# power_supply.net
KiCad netlist of a schematic drawn in Altium Designer
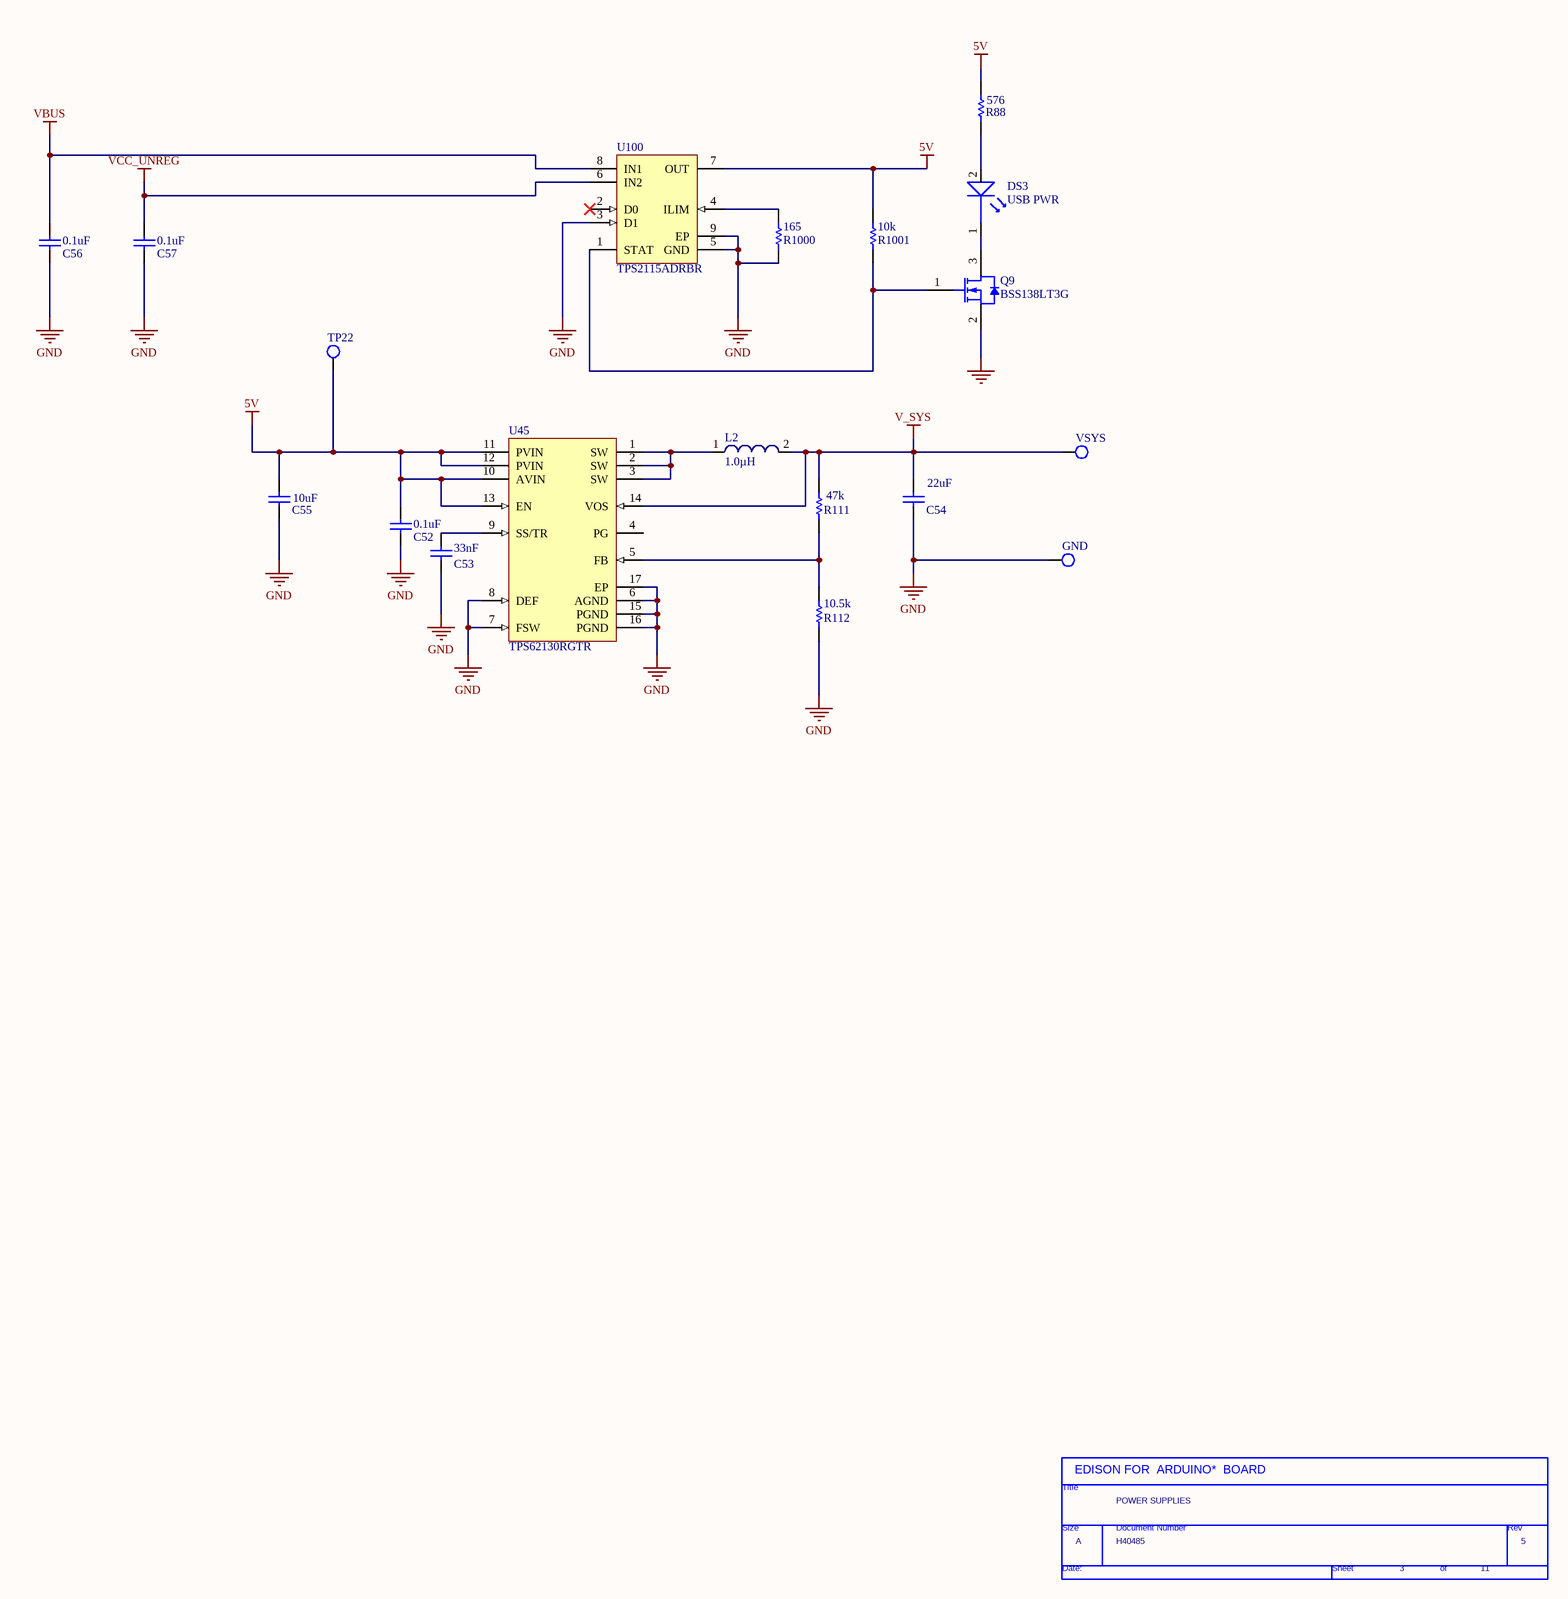
[diagram p0: power_supply.SchDoc]

(export (version "E")
  (design (tool "Eeschema 10.0.6"))
  (components
    (comp (ref "C52")
      (value "0.1uF")
      (footprint "CAPC0805(2012)145_L")
      (description "CAP 100nF 16V ±10% 0805 (2012 Metric) Thickness 1.45mm SMD")
      (fields (field (name "TOLERANCE") "±10%") (field (name "Comment") "CAP 100nF 16V 0805(2012)"))
      (libsource (lib "Altium Content Vault") (part "CMP-1036-04401-1"))
    )
    (comp (ref "C53")
      (value "33nF")
      (footprint "CAPC0805(2012)145_L")
      (description "CAP 33nF 50V ±10% 0805 (2012 Metric) Thickness 1.45mm SMD")
      (fields (field (name "TOLERANCE") "±10%") (field (name "Comment") "CAP 33nF 50V 0805(2012)"))
      (libsource (lib "Altium Content Vault") (part "CMP-1036-04168-1"))
    )
    (comp (ref "C54")
      (value "22uF")
      (footprint "CAPC0805(2012)145_M")
      (description "CAP 22uF 6.3V ±20% 0805 (2012 Metric) Thickness 1.45mm SMD")
      (fields (field (name "TOLERANCE") "±20%") (field (name "Comment") "CAP 22uF 6.3V 0805(2012)"))
      (libsource (lib "Altium Content Vault") (part "CMP-1036-04939-1"))
    )
    (comp (ref "C55")
      (value "10uF")
      (footprint "CAPC0805(2012)145_L")
      (description "CAP 820pF 25V ±10% 0805 (2012 Metric) Thickness 1.45mm SMD")
      (fields (field (name "TOLERANCE") "±10%") (field (name "Comment") "CAP 820pF 25V 0805(2012)"))
      (libsource (lib "Altium Content Vault") (part "CMP-1036-02893-1"))
    )
    (comp (ref "C56")
      (value "0.1uF")
      (footprint "CAPC0805(2012)145_L")
      (description "CAP 100nF 16V ±10% 0805 (2012 Metric) Thickness 1.45mm SMD")
      (fields (field (name "TOLERANCE") "±10%") (field (name "Comment") "CAP 100nF 16V 0805(2012)"))
      (libsource (lib "Altium Content Vault") (part "CMP-1036-04401-1"))
    )
    (comp (ref "C57")
      (value "0.1uF")
      (footprint "CAPC0805(2012)145_L")
      (description "CAP 100nF 16V ±10% 0805 (2012 Metric) Thickness 1.45mm SMD")
      (fields (field (name "TOLERANCE") "±10%") (field (name "Comment") "CAP 100nF 16V 0805(2012)"))
      (libsource (lib "Altium Content Vault") (part "CMP-1036-04401-1"))
    )
    (comp (ref "DS3")
      (value "USB PWR")
      (footprint "LTST-C281KGKT")
      (libsource (lib "elevate_lib") (part "LED_Edison"))
    )
    (comp (ref "GND")
      (value "Testpoint")
      (footprint "Tespoint_Keystone")
      (libsource (lib "elevate_lib") (part "TestPoint"))
    )
    (comp (ref "L2")
      (value "1.0µH")
      (footprint "SMD 2508")
      (description "Power Multilayer Inductor WE-MAPI, L=1.0µH")
      (fields
        (field (name "PARTNO") "74438322010")
        (field (name "MANUFACTURER") "Würth Elektronik eiSos GmbH")
        (field (name "CREATED BY") "Otto Christin")
      )
      (libsource (lib "WE-MAPI_2508") (part "WE-MAPI 2508 ,74438322010"))
    )
    (comp (ref "Q9")
      (value "BSS138LT3G")
      (footprint "ONSC-SOT-23-3-318-08_V")
      (description "Power MOSFET, 200 mA, 50 V, N-Channel, 3-Pin SOT-23, Pb-Free, Tape and Reel")
      (fields (field (name "MANUFACTURER") "On Semiconductor"))
      (libsource (lib "Altium Content Vault") (part "CMP-1058-00765-1"))
    )
    (comp (ref "R88")
      (value "576")
      (footprint "RESC0603(1608)_N")
      (description "576R 0.1W 1% 0603 (1608 Metric)  SMD")
      (fields (field (name "TOLERANCE") "1 %") (field (name "POWER") "0.1 W"))
      (libsource (lib "Altium Content Vault") (part "CMP-1012-00483-1"))
    )
    (comp (ref "R111")
      (value "47k")
      (footprint "RESC0603(1608)_N")
      (description "47K 0.1W 1% 0603 (1608 Metric)  SMD")
      (fields (field (name "POWER") "0.1 W") (field (name "TOLERANCE") "1 %"))
      (libsource (lib "Altium Content Vault") (part "CMP-1012-00699-1"))
    )
    (comp (ref "R112")
      (value "10.5k")
      (footprint "RESC0603(1608)_N")
      (description "10K5 0.1W 1% 0603 (1608 Metric)  SMD")
      (fields (field (name "POWER") "0.1 W") (field (name "TOLERANCE") "1 %"))
      (libsource (lib "Altium Content Vault") (part "CMP-1012-00625-1"))
    )
    (comp (ref "R1000")
      (value "165")
      (footprint "RESC0805(2012)_L")
      (description "165R 0.125W 1% 0805 (2012 Metric)  SMD")
      (fields (field (name "TOLERANCE") "1 %") (field (name "POWER") "0.125 W"))
      (libsource (lib "Altium Content Vault") (part "CMP-1013-00420-1"))
    )
    (comp (ref "R1001")
      (value "10k")
      (footprint "RESC0805(2012)_M")
      (description "10K 0.125W 1% 0805 (2012 Metric)  SMD")
      (fields (field (name "TOLERANCE") "1 %") (field (name "POWER") "0.125 W"))
      (libsource (lib "Altium Content Vault") (part "CMP-1013-00623-1"))
    )
    (comp (ref "TP22")
      (value "Testpoint")
      (footprint "Tespoint_Keystone")
      (libsource (lib "elevate_lib") (part "TestPoint"))
    )
    (comp (ref "U45")
      (value "TPS62130RGTR")
      (footprint "RGT16-1700X1700TP")
      (fields (field (name "MANUFACTURER") "Texas Instruments"))
      (libsource (lib "Altium Content Vault") (part "CMP-0323-00115-2"))
    )
    (comp (ref "U100")
      (value "TPS2115ADRBR")
      (footprint "DRB8-2400X1650TP")
      (fields (field (name "MANUFACTURER") "Texas Instruments"))
      (libsource (lib "TI Power Management Power Multiplexer (MUX)") (part "TPS2115ADRBR"))
    )
    (comp (ref "VSYS")
      (value "Testpoint")
      (footprint "Tespoint_Keystone")
      (libsource (lib "elevate_lib") (part "TestPoint"))
    )
  )
  (nets
    (net (code "1") (name "5V") (class "Default")
      (node (ref "C52") (pin "1") (pinfunction "1_1") (pintype "passive"))
      (node (ref "C55") (pin "2") (pinfunction "2_2") (pintype "passive"))
      (node (ref "R1001") (pin "2") (pinfunction "2_2") (pintype "passive"))
      (node (ref "R88") (pin "2") (pinfunction "2_2") (pintype "passive"))
      (node (ref "TP22") (pin "1") (pinfunction "TP_1") (pintype "passive"))
      (node (ref "U100") (pin "7") (pinfunction "OUT_7") (pintype "power_in"))
      (node (ref "U45") (pin "10") (pinfunction "AVIN_10") (pintype "power_in"))
      (node (ref "U45") (pin "11") (pinfunction "PVIN_11") (pintype "power_in"))
      (node (ref "U45") (pin "12") (pinfunction "PVIN_12") (pintype "power_in"))
      (node (ref "U45") (pin "13") (pinfunction "EN_13") (pintype "input"))
    )
    (net (code "2") (name "GND") (class "Default")
      (node (ref "C52") (pin "2") (pinfunction "2_2") (pintype "passive"))
      (node (ref "C53") (pin "1") (pinfunction "1_1") (pintype "passive"))
      (node (ref "C54") (pin "1") (pinfunction "1_1") (pintype "passive"))
      (node (ref "C55") (pin "1") (pinfunction "1_1") (pintype "passive"))
      (node (ref "C56") (pin "2") (pinfunction "2_2") (pintype "passive"))
      (node (ref "C57") (pin "2") (pinfunction "2_2") (pintype "passive"))
      (node (ref "GND") (pin "1") (pinfunction "TP_1") (pintype "passive"))
      (node (ref "Q9") (pin "2") (pinfunction "S_2") (pintype "passive"))
      (node (ref "R1000") (pin "1") (pinfunction "1_1") (pintype "passive"))
      (node (ref "R112") (pin "1") (pinfunction "1_1") (pintype "passive"))
      (node (ref "U100") (pin "3") (pinfunction "D1_3") (pintype "input"))
      (node (ref "U100") (pin "5") (pinfunction "GND_5") (pintype "power_in"))
      (node (ref "U100") (pin "9") (pinfunction "EP_9") (pintype "power_in"))
      (node (ref "U45") (pin "15") (pinfunction "PGND_15") (pintype "power_in"))
      (node (ref "U45") (pin "16") (pinfunction "PGND_16") (pintype "power_in"))
      (node (ref "U45") (pin "17") (pinfunction "EP_17") (pintype "power_in"))
      (node (ref "U45") (pin "6") (pinfunction "AGND_6") (pintype "power_in"))
      (node (ref "U45") (pin "7") (pinfunction "FSW_7") (pintype "input"))
      (node (ref "U45") (pin "8") (pinfunction "DEF_8") (pintype "input"))
    )
    (net (code "3") (name "Net-(DS3-LED1)") (class "Default")
      (node (ref "DS3") (pin "1") (pinfunction "LED1_1") (pintype "passive"))
      (node (ref "Q9") (pin "3") (pinfunction "D_3") (pintype "passive"))
    )
    (net (code "4") (name "Net-(DS3-LED2)") (class "Default")
      (node (ref "DS3") (pin "2") (pinfunction "LED2_2") (pintype "passive"))
      (node (ref "R88") (pin "1") (pinfunction "1_1") (pintype "passive"))
    )
    (net (code "5") (name "Net-(L2-Pad1)") (class "Default")
      (node (ref "L2") (pin "1") (pinfunction "1_1") (pintype "passive"))
      (node (ref "U45") (pin "1") (pinfunction "SW_1") (pintype "power_in"))
      (node (ref "U45") (pin "2") (pinfunction "SW_2") (pintype "power_in"))
      (node (ref "U45") (pin "3") (pinfunction "SW_3") (pintype "power_in"))
    )
    (net (code "6") (name "Net-(Q9-G)") (class "Default")
      (node (ref "Q9") (pin "1") (pinfunction "G_1") (pintype "passive"))
      (node (ref "R1001") (pin "1") (pinfunction "1_1") (pintype "passive"))
      (node (ref "U100") (pin "1") (pinfunction "STAT_1") (pintype "tri_state"))
    )
    (net (code "7") (name "Net-(U45-FB)") (class "Default")
      (node (ref "R111") (pin "1") (pinfunction "1_1") (pintype "passive"))
      (node (ref "R112") (pin "2") (pinfunction "2_2") (pintype "passive"))
      (node (ref "U45") (pin "5") (pinfunction "FB_5") (pintype "input"))
    )
    (net (code "8") (name "Net-(U45-SS{slash}TR)") (class "Default")
      (node (ref "C53") (pin "2") (pinfunction "2_2") (pintype "passive"))
      (node (ref "U45") (pin "9") (pinfunction "SS/TR_9") (pintype "input"))
    )
    (net (code "9") (name "Net-(U100-ILIM)") (class "Default")
      (node (ref "R1000") (pin "2") (pinfunction "2_2") (pintype "passive"))
      (node (ref "U100") (pin "4") (pinfunction "ILIM_4") (pintype "input"))
    )
    (net (code "10") (name "VBUS") (class "Default")
      (node (ref "C56") (pin "1") (pinfunction "1_1") (pintype "passive"))
      (node (ref "U100") (pin "8") (pinfunction "IN1_8") (pintype "power_in"))
    )
    (net (code "11") (name "VCC_UNREG") (class "Default")
      (node (ref "C57") (pin "1") (pinfunction "1_1") (pintype "passive"))
      (node (ref "U100") (pin "6") (pinfunction "IN2_6") (pintype "power_in"))
    )
    (net (code "12") (name "V_SYS") (class "Default")
      (node (ref "C54") (pin "2") (pinfunction "2_2") (pintype "passive"))
      (node (ref "L2") (pin "2") (pinfunction "2_2") (pintype "passive"))
      (node (ref "R111") (pin "2") (pinfunction "2_2") (pintype "passive"))
      (node (ref "U45") (pin "14") (pinfunction "VOS_14") (pintype "input"))
      (node (ref "VSYS") (pin "1") (pinfunction "TP_1") (pintype "passive"))
    )
    (net (code "13") (name "unconnected-(U45-PG-Pad4)") (class "Default")
      (node (ref "U45") (pin "4") (pinfunction "PG_4") (pintype "tri_state"))
    )
    (net (code "14") (name "unconnected-(U100-D0-Pad2)") (class "Default")
      (node (ref "U100") (pin "2") (pinfunction "D0_2") (pintype "input+no_connect"))
    )
  )
)
